# Power_Monitor.net
KiCad netlist of a schematic drawn in Altium Designer
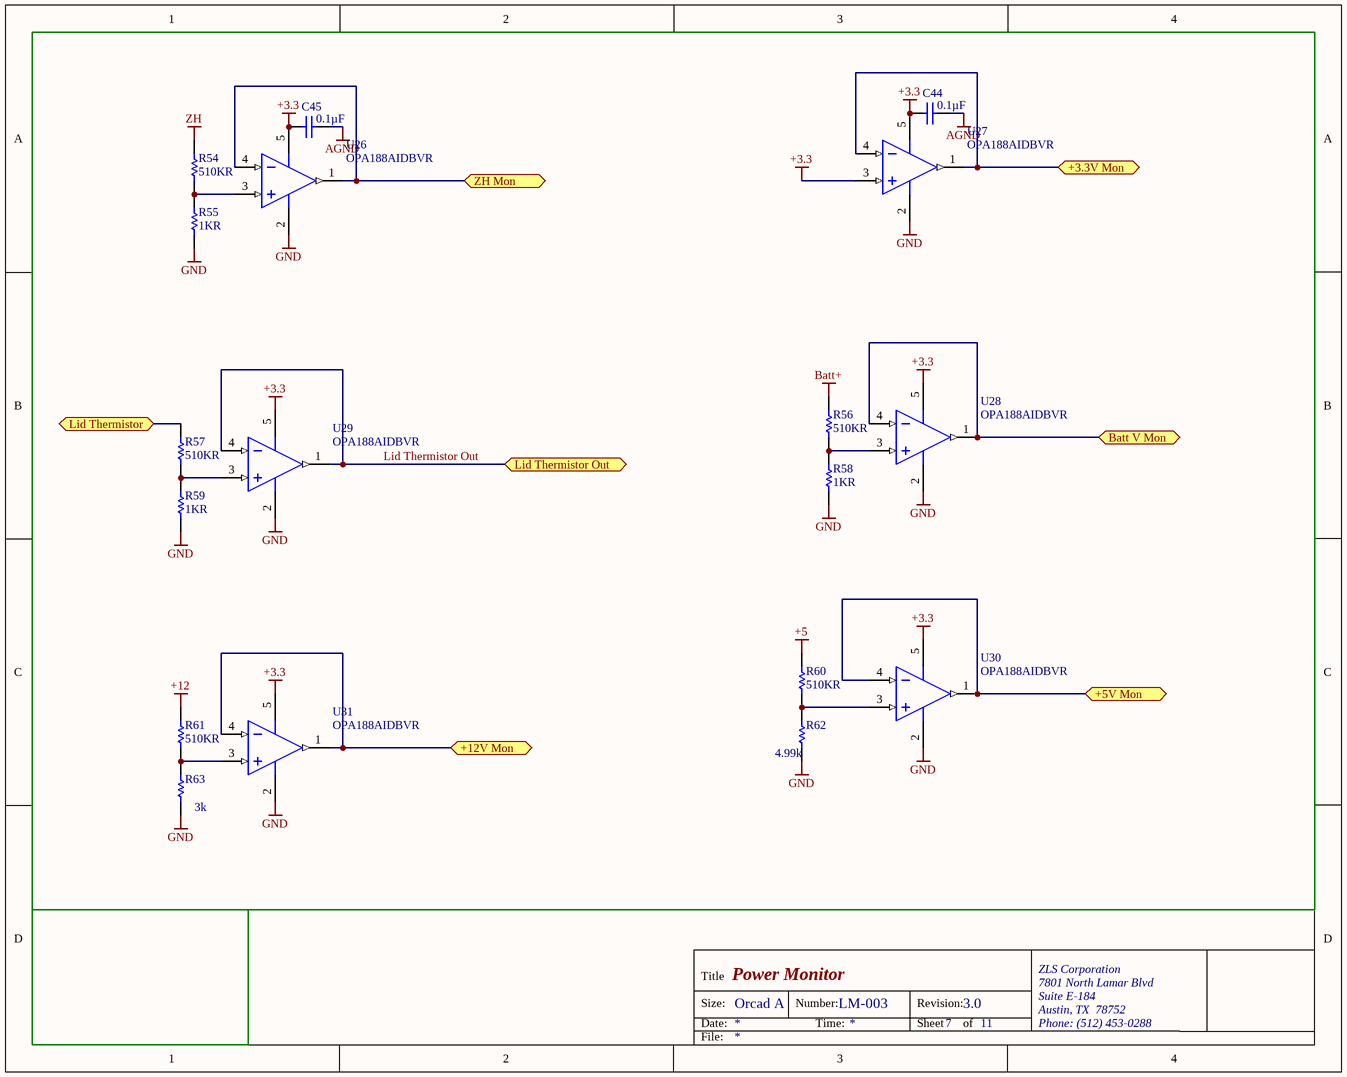
[diagram p0: Power Monitor.SchDoc]

(export (version "E")
  (design (tool "Eeschema 10.0.6"))
  (components
    (comp (ref "C44")
      (value "CAP CER 0.1UF 25V X7R 0805")
      (footprint "CAPC0805(2012)145_N")
      (fields
        (field (name "MANUFACTURER") "Murata Electronics North America")
        (field (name "MANUFACTURER PART NUMBER") "GRM21BR71E104KA01L")
        (field (name "CAPACITANCE") "0.1µF")
        (field (name "TOLERANCE") "±10%")
      )
      (libsource (lib "Altium Content Vault") (part "CMP-1036-04795-1"))
    )
    (comp (ref "C45")
      (value "CAP CER 0.1UF 25V X7R 0805")
      (footprint "CAPC0805(2012)145_N")
      (fields
        (field (name "MANUFACTURER") "Murata Electronics North America")
        (field (name "MANUFACTURER PART NUMBER") "GRM21BR71E104KA01L")
        (field (name "CAPACITANCE") "0.1µF")
        (field (name "TOLERANCE") "±10%")
      )
      (libsource (lib "Altium Content Vault") (part "CMP-1036-04795-1"))
    )
    (comp (ref "R54")
      (value "RES SMD 510K OHM 1% 1/16W 0402")
      (footprint "RESC0402(1005)_M")
      (fields
        (field (name "MANUFACTURER") "Vishay")
        (field (name "MANUFACTURER PART NUMBER") "CRCW0402510KFKED")
        (field (name "RESISTANCE") "510KR")
        (field (name "TOLERANCE") "1%")
      )
      (libsource (lib "Altium Content Vault") (part "CMP-1011-00651-1"))
    )
    (comp (ref "R55")
      (value "RES SMD 1K OHM 1% 1/16W 0402")
      (footprint "RESC0402(1005)_M")
      (fields
        (field (name "MANUFACTURER") "Yageo")
        (field (name "MANUFACTURER PART NUMBER") "RC0402FR-071KL")
        (field (name "TOLERANCE") "1%")
        (field (name "RESISTANCE") "1KR")
      )
      (libsource (lib "Altium Content Vault") (part "CMP-1011-00651-1"))
    )
    (comp (ref "R56")
      (value "RES SMD 510K OHM 1% 1/16W 0402")
      (footprint "RESC0402(1005)_M")
      (fields
        (field (name "MANUFACTURER") "Vishay")
        (field (name "MANUFACTURER PART NUMBER") "CRCW0402510KFKED")
        (field (name "RESISTANCE") "510KR")
        (field (name "TOLERANCE") "1%")
      )
      (libsource (lib "Altium Content Vault") (part "CMP-1011-00651-1"))
    )
    (comp (ref "R57")
      (value "RES SMD 510K OHM 1% 1/16W 0402")
      (footprint "RESC0402(1005)_M")
      (fields
        (field (name "MANUFACTURER") "Vishay")
        (field (name "MANUFACTURER PART NUMBER") "CRCW0402510KFKED")
        (field (name "RESISTANCE") "510KR")
        (field (name "TOLERANCE") "1%")
      )
      (libsource (lib "Altium Content Vault") (part "CMP-1011-00651-1"))
    )
    (comp (ref "R58")
      (value "RES SMD 1K OHM 1% 1/16W 0402")
      (footprint "RESC0402(1005)_M")
      (fields
        (field (name "MANUFACTURER") "Yageo")
        (field (name "MANUFACTURER PART NUMBER") "RC0402FR-071KL")
        (field (name "TOLERANCE") "1%")
        (field (name "RESISTANCE") "1KR")
      )
      (libsource (lib "Altium Content Vault") (part "CMP-1011-00651-1"))
    )
    (comp (ref "R59")
      (value "RES SMD 1K OHM 1% 1/16W 0402")
      (footprint "RESC0402(1005)_M")
      (fields
        (field (name "MANUFACTURER") "Yageo")
        (field (name "MANUFACTURER PART NUMBER") "RC0402FR-071KL")
        (field (name "TOLERANCE") "1%")
        (field (name "RESISTANCE") "1KR")
      )
      (libsource (lib "Altium Content Vault") (part "CMP-1011-00651-1"))
    )
    (comp (ref "R60")
      (value "RES SMD 510K OHM 1% 1/16W 0402")
      (footprint "RESC0402(1005)_M")
      (fields
        (field (name "MANUFACTURER") "Vishay")
        (field (name "MANUFACTURER PART NUMBER") "CRCW0402510KFKED")
        (field (name "RESISTANCE") "510KR")
        (field (name "TOLERANCE") "1%")
      )
      (libsource (lib "Altium Content Vault") (part "CMP-1011-00651-1"))
    )
    (comp (ref "R61")
      (value "RES SMD 510K OHM 1% 1/16W 0402")
      (footprint "RESC0402(1005)_M")
      (fields
        (field (name "MANUFACTURER") "Vishay")
        (field (name "MANUFACTURER PART NUMBER") "CRCW0402510KFKED")
        (field (name "RESISTANCE") "510KR")
        (field (name "TOLERANCE") "1%")
      )
      (libsource (lib "Altium Content Vault") (part "CMP-1011-00651-1"))
    )
    (comp (ref "R62")
      (value "RES SMD 4.99K OHM 1% 1/8W 0805")
      (footprint "RESC0805(2012)_L")
      (fields
        (field (name "MANUFACTURER") "Vishay Dale")
        (field (name "MANUFACTURER PART NUMBER") "CRCW08054K99FKTA")
        (field (name "RESISTANCE (OHMS)") "4.99k")
        (field (name "TOLERANCE") "±1%")
      )
      (libsource (lib "Altium Content Vault") (part "CMP-1013-00393-1"))
    )
    (comp (ref "R63")
      (value "RES SMD 3K OHM 1% 1/2W 0805")
      (footprint "RESC0805(2012)_L")
      (fields
        (field (name "MANUFACTURER") "Vishay Dale")
        (field (name "MANUFACTURER PART NUMBER") "CRCW08053K00FKEAHP")
        (field (name "RESISTANCE (OHMS)") "3k")
        (field (name "TOLERANCE") "±1%")
      )
      (libsource (lib "Altium Content Vault") (part "CMP-1013-00393-1"))
    )
    (comp (ref "U26")
      (value "OPA188AIDBVR")
      (footprint "DBV0005A_M")
      (fields (field (name "MANUFACTURER") "Texas Instruments"))
      (libsource (lib "Altium Content Vault") (part "CMP-0809-00005-2"))
    )
    (comp (ref "U27")
      (value "OPA188AIDBVR")
      (footprint "DBV0005A_M")
      (fields (field (name "MANUFACTURER") "Texas Instruments"))
      (libsource (lib "Altium Content Vault") (part "CMP-0809-00005-2"))
    )
    (comp (ref "U28")
      (value "OPA188AIDBVR")
      (footprint "DBV0005A_M")
      (fields (field (name "MANUFACTURER") "Texas Instruments"))
      (libsource (lib "Altium Content Vault") (part "CMP-0809-00005-2"))
    )
    (comp (ref "U29")
      (value "OPA188AIDBVR")
      (footprint "DBV0005A_M")
      (fields (field (name "MANUFACTURER") "Texas Instruments"))
      (libsource (lib "Altium Content Vault") (part "CMP-0809-00005-2"))
    )
    (comp (ref "U30")
      (value "OPA188AIDBVR")
      (footprint "DBV0005A_M")
      (fields (field (name "MANUFACTURER") "Texas Instruments"))
      (libsource (lib "Altium Content Vault") (part "CMP-0809-00005-2"))
    )
    (comp (ref "U31")
      (value "OPA188AIDBVR")
      (footprint "DBV0005A_M")
      (fields (field (name "MANUFACTURER") "Texas Instruments"))
      (libsource (lib "Altium Content Vault") (part "CMP-0809-00005-2"))
    )
  )
  (nets
    (net (code "1") (name "+3.3") (class "Default")
      (node (ref "C44") (pin "1") (pinfunction "1_1") (pintype "passive"))
      (node (ref "C45") (pin "1") (pinfunction "1_1") (pintype "passive"))
      (node (ref "U26") (pin "5") (pinfunction "V+_5") (pintype "power_in"))
      (node (ref "U27") (pin "3") (pinfunction "IN+_3") (pintype "input"))
      (node (ref "U27") (pin "5") (pinfunction "V+_5") (pintype "power_in"))
      (node (ref "U28") (pin "5") (pinfunction "V+_5") (pintype "power_in"))
      (node (ref "U29") (pin "5") (pinfunction "V+_5") (pintype "power_in"))
      (node (ref "U30") (pin "5") (pinfunction "V+_5") (pintype "power_in"))
      (node (ref "U31") (pin "5") (pinfunction "V+_5") (pintype "power_in"))
    )
    (net (code "2") (name "+5") (class "Default")
      (node (ref "R60") (pin "2") (pinfunction "2_2") (pintype "passive"))
    )
    (net (code "3") (name "+12") (class "Default")
      (node (ref "R61") (pin "2") (pinfunction "2_2") (pintype "passive"))
    )
    (net (code "4") (name "/+3.3V Mon") (class "Default")
      (node (ref "U27") (pin "1") (pinfunction "OUT_1") (pintype "output"))
      (node (ref "U27") (pin "4") (pinfunction "IN-_4") (pintype "input"))
    )
    (net (code "5") (name "/+5V Mon") (class "Default")
      (node (ref "U30") (pin "1") (pinfunction "OUT_1") (pintype "output"))
      (node (ref "U30") (pin "4") (pinfunction "IN-_4") (pintype "input"))
    )
    (net (code "6") (name "/+12V Mon") (class "Default")
      (node (ref "U31") (pin "1") (pinfunction "OUT_1") (pintype "output"))
      (node (ref "U31") (pin "4") (pinfunction "IN-_4") (pintype "input"))
    )
    (net (code "7") (name "/Batt V Mon") (class "Default")
      (node (ref "U28") (pin "1") (pinfunction "OUT_1") (pintype "output"))
      (node (ref "U28") (pin "4") (pinfunction "IN-_4") (pintype "input"))
    )
    (net (code "8") (name "/Lid Thermistor") (class "Default")
      (node (ref "R57") (pin "2") (pinfunction "2_2") (pintype "passive"))
    )
    (net (code "9") (name "/Lid Thermistor Out") (class "Default")
      (node (ref "U29") (pin "1") (pinfunction "OUT_1") (pintype "output"))
      (node (ref "U29") (pin "4") (pinfunction "IN-_4") (pintype "input"))
    )
    (net (code "10") (name "/ZH Mon") (class "Default")
      (node (ref "U26") (pin "1") (pinfunction "OUT_1") (pintype "output"))
      (node (ref "U26") (pin "4") (pinfunction "IN-_4") (pintype "input"))
    )
    (net (code "11") (name "AGND") (class "Default")
      (node (ref "C44") (pin "2") (pinfunction "2_2") (pintype "passive"))
      (node (ref "C45") (pin "2") (pinfunction "2_2") (pintype "passive"))
    )
    (net (code "12") (name "Batt+") (class "Default")
      (node (ref "R56") (pin "2") (pinfunction "2_2") (pintype "passive"))
    )
    (net (code "13") (name "GND") (class "Default")
      (node (ref "R55") (pin "1") (pinfunction "1_1") (pintype "passive"))
      (node (ref "R58") (pin "1") (pinfunction "1_1") (pintype "passive"))
      (node (ref "R59") (pin "1") (pinfunction "1_1") (pintype "passive"))
      (node (ref "R62") (pin "1") (pinfunction "1_1") (pintype "passive"))
      (node (ref "R63") (pin "1") (pinfunction "1_1") (pintype "passive"))
      (node (ref "U26") (pin "2") (pinfunction "V-_2") (pintype "power_in"))
      (node (ref "U27") (pin "2") (pinfunction "V-_2") (pintype "power_in"))
      (node (ref "U28") (pin "2") (pinfunction "V-_2") (pintype "power_in"))
      (node (ref "U29") (pin "2") (pinfunction "V-_2") (pintype "power_in"))
      (node (ref "U30") (pin "2") (pinfunction "V-_2") (pintype "power_in"))
      (node (ref "U31") (pin "2") (pinfunction "V-_2") (pintype "power_in"))
    )
    (net (code "14") (name "Net-(U26-IN+)") (class "Default")
      (node (ref "R54") (pin "1") (pinfunction "1_1") (pintype "passive"))
      (node (ref "R55") (pin "2") (pinfunction "2_2") (pintype "passive"))
      (node (ref "U26") (pin "3") (pinfunction "IN+_3") (pintype "input"))
    )
    (net (code "15") (name "Net-(U28-IN+)") (class "Default")
      (node (ref "R56") (pin "1") (pinfunction "1_1") (pintype "passive"))
      (node (ref "R58") (pin "2") (pinfunction "2_2") (pintype "passive"))
      (node (ref "U28") (pin "3") (pinfunction "IN+_3") (pintype "input"))
    )
    (net (code "16") (name "Net-(U29-IN+)") (class "Default")
      (node (ref "R57") (pin "1") (pinfunction "1_1") (pintype "passive"))
      (node (ref "R59") (pin "2") (pinfunction "2_2") (pintype "passive"))
      (node (ref "U29") (pin "3") (pinfunction "IN+_3") (pintype "input"))
    )
    (net (code "17") (name "Net-(U30-IN+)") (class "Default")
      (node (ref "R60") (pin "1") (pinfunction "1_1") (pintype "passive"))
      (node (ref "R62") (pin "2") (pinfunction "2_2") (pintype "passive"))
      (node (ref "U30") (pin "3") (pinfunction "IN+_3") (pintype "input"))
    )
    (net (code "18") (name "Net-(U31-IN+)") (class "Default")
      (node (ref "R61") (pin "1") (pinfunction "1_1") (pintype "passive"))
      (node (ref "R63") (pin "2") (pinfunction "2_2") (pintype "passive"))
      (node (ref "U31") (pin "3") (pinfunction "IN+_3") (pintype "input"))
    )
    (net (code "19") (name "ZH") (class "Default")
      (node (ref "R54") (pin "2") (pinfunction "2_2") (pintype "passive"))
    )
  )
)
